# MM2017-18_uC_Main.net
KiCad netlist of a schematic drawn in EAGLE
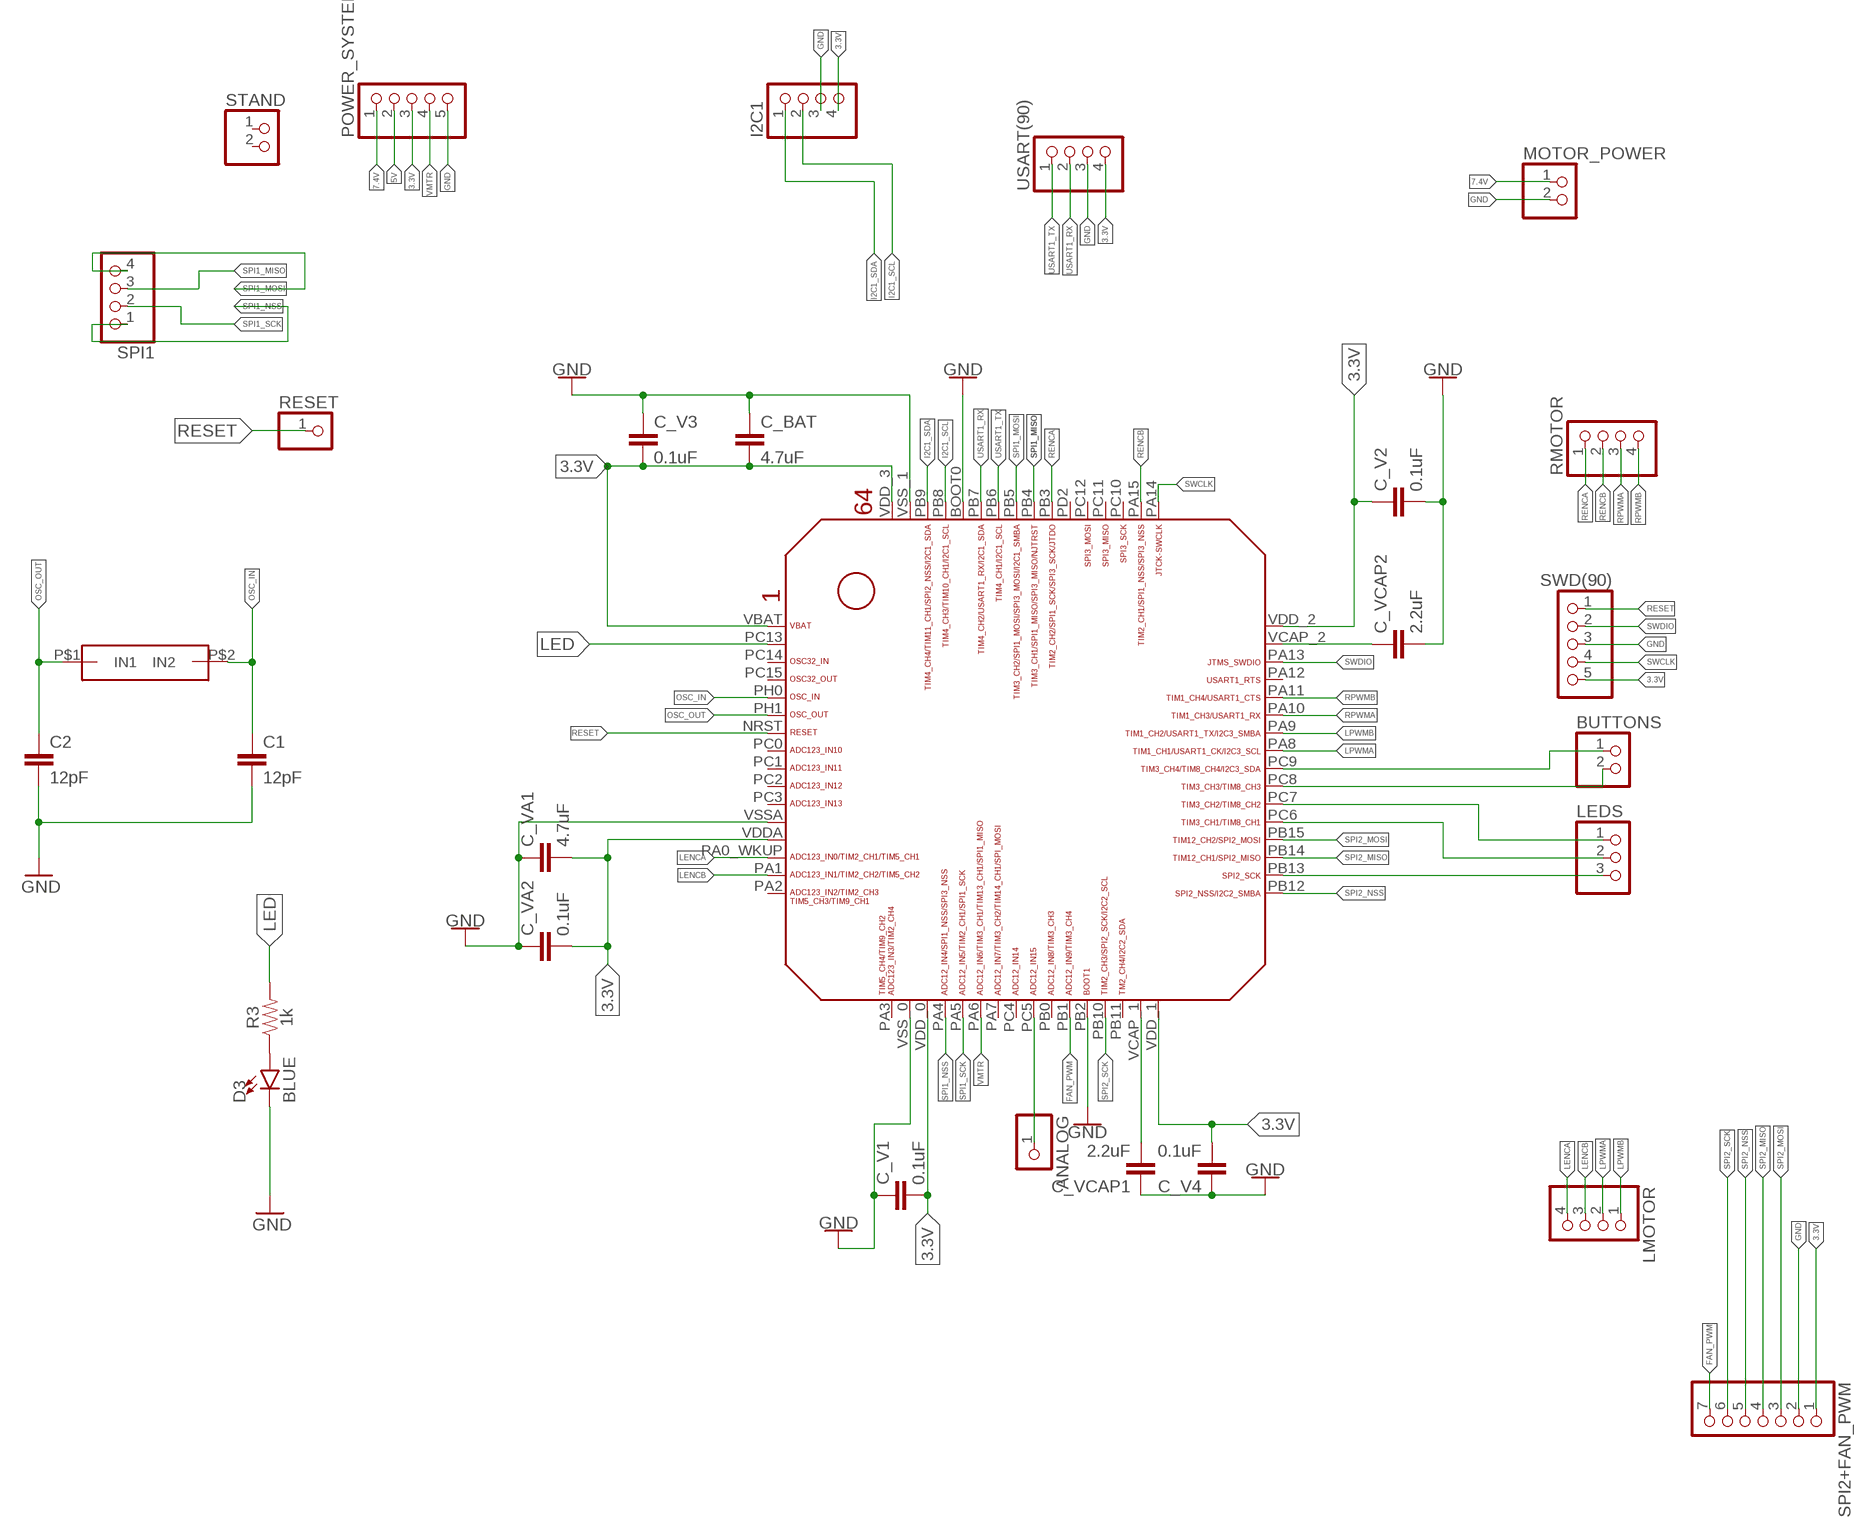
[diagram p0: schematic, sheet 1]

(export (version "E")
  (design (tool "Eeschema 10.0.6"))
  (components
    (comp (ref "ANALOG")
      (value "PINHD-1X1")
      (footprint "eagle-import:1X01")
      (libsource (lib "eagle-import") (part "PINHD-1X1"))
    )
    (comp (ref "BUTTONS")
      (value "PINHD-1X2")
      (footprint "eagle-import:1X02")
      (libsource (lib "eagle-import") (part "PINHD-1X2"))
    )
    (comp (ref "C1")
      (value "12pF")
      (footprint "eagle-import:0603")
      (libsource (lib "eagle-import") (part "22PF-0603-50V-5%"))
    )
    (comp (ref "C2")
      (value "12pF")
      (footprint "eagle-import:0603")
      (libsource (lib "eagle-import") (part "22PF-0603-50V-5%"))
    )
    (comp (ref "C_BAT")
      (value "4.7uF")
      (footprint "eagle-import:0805")
      (libsource (lib "eagle-import") (part "22UF-0805-6.3V-20%"))
    )
    (comp (ref "C_V1")
      (value "0.1uF")
      (footprint "eagle-import:0805")
      (libsource (lib "eagle-import") (part "22UF-0805-6.3V-20%"))
    )
    (comp (ref "C_V2")
      (value "0.1uF")
      (footprint "eagle-import:0805")
      (libsource (lib "eagle-import") (part "22UF-0805-6.3V-20%"))
    )
    (comp (ref "C_V3")
      (value "0.1uF")
      (footprint "eagle-import:0805")
      (libsource (lib "eagle-import") (part "22UF-0805-6.3V-20%"))
    )
    (comp (ref "C_V4")
      (value "0.1uF")
      (footprint "eagle-import:0805")
      (libsource (lib "eagle-import") (part "22UF-0805-6.3V-20%"))
    )
    (comp (ref "C_VA1")
      (value "4.7uF")
      (footprint "eagle-import:0805")
      (libsource (lib "eagle-import") (part "22UF-0805-6.3V-20%"))
    )
    (comp (ref "C_VA2")
      (value "0.1uF")
      (footprint "eagle-import:0805")
      (libsource (lib "eagle-import") (part "22UF-0805-6.3V-20%"))
    )
    (comp (ref "C_VCAP1")
      (value "2.2uF")
      (footprint "eagle-import:0805")
      (libsource (lib "eagle-import") (part "22UF-0805-6.3V-20%"))
    )
    (comp (ref "C_VCAP2")
      (value "2.2uF")
      (footprint "eagle-import:0805")
      (libsource (lib "eagle-import") (part "22UF-0805-6.3V-20%"))
    )
    (comp (ref "D3")
      (value "BLUE")
      (footprint "eagle-import:LED-1206")
      (libsource (lib "eagle-import") (part "LED-BLUE1206"))
    )
    (comp (ref "I2C1")
      (value "PINHD-1X4")
      (footprint "eagle-import:1X04")
      (libsource (lib "eagle-import") (part "PINHD-1X4"))
    )
    (comp (ref "LEDS")
      (value "PINHD-1X3")
      (footprint "eagle-import:1X03")
      (libsource (lib "eagle-import") (part "PINHD-1X3"))
    )
    (comp (ref "LMOTOR")
      (value "PINHD-1X4")
      (footprint "eagle-import:1X04")
      (libsource (lib "eagle-import") (part "PINHD-1X4"))
    )
    (comp (ref "MOTOR_POWER")
      (value "PINHD-1X2")
      (footprint "eagle-import:1X02")
      (libsource (lib "eagle-import") (part "PINHD-1X2"))
    )
    (comp (ref "POWER_SYSTEM")
      (value "PINHD-1X5")
      (footprint "eagle-import:1X05")
      (libsource (lib "eagle-import") (part "PINHD-1X5"))
    )
    (comp (ref "R3")
      (value "1k")
      (footprint "eagle-import:0805")
      (libsource (lib "eagle-import") (part "0.75OHM-0805-1/4W-1%"))
    )
    (comp (ref "RESET")
      (value "PINHD-1X1")
      (footprint "eagle-import:1X01")
      (libsource (lib "eagle-import") (part "PINHD-1X1"))
    )
    (comp (ref "RMOTOR")
      (value "PINHD-1X4")
      (footprint "eagle-import:1X04")
      (libsource (lib "eagle-import") (part "PINHD-1X4"))
    )
    (comp (ref "SPI1")
      (value "PINHD-1X4")
      (footprint "eagle-import:1X04")
      (libsource (lib "eagle-import") (part "PINHD-1X4"))
    )
    (comp (ref "SPI2+FAN_PWM")
      (value "PINHD-1X7")
      (footprint "eagle-import:1X07")
      (libsource (lib "eagle-import") (part "PINHD-1X7"))
    )
    (comp (ref "STAND")
      (value "PINHD-1X2")
      (footprint "eagle-import:1X02")
      (libsource (lib "eagle-import") (part "PINHD-1X2"))
    )
    (comp (ref "SWD(90)")
      (value "PINHD-1X5")
      (footprint "eagle-import:1X05")
      (libsource (lib "eagle-import") (part "PINHD-1X5"))
    )
    (comp (ref "U$1")
      (value "STM32F405/415_LQFP64")
      (footprint "eagle-import:STM32F405_415_LQFP64")
      (libsource (lib "eagle-import") (part "STM32F405/415_LQFP64"))
    )
    (comp (ref "U$2")
      (value "OSC")
      (footprint "eagle-import:OSC")
      (libsource (lib "eagle-import") (part "OSC"))
    )
    (comp (ref "USART(90)")
      (value "PINHD-1X4")
      (footprint "eagle-import:1X04")
      (libsource (lib "eagle-import") (part "PINHD-1X4"))
    )
  )
  (nets
    (net (code "1") (name "3.3V") (class "Default")
      (node (ref "C_BAT") (pin "2") (pinfunction "2_2") (pintype "passive"))
      (node (ref "C_V1") (pin "2") (pinfunction "2_2") (pintype "passive"))
      (node (ref "C_V2") (pin "1") (pinfunction "1_1") (pintype "passive"))
      (node (ref "C_V3") (pin "2") (pinfunction "2_2") (pintype "passive"))
      (node (ref "C_V4") (pin "2") (pinfunction "2_2") (pintype "passive"))
      (node (ref "C_VA1") (pin "2") (pinfunction "2_2") (pintype "passive"))
      (node (ref "C_VA2") (pin "2") (pinfunction "2_2") (pintype "passive"))
      (node (ref "I2C1") (pin "4") (pinfunction "4_4") (pintype "passive"))
      (node (ref "POWER_SYSTEM") (pin "3") (pinfunction "3_3") (pintype "passive"))
      (node (ref "SPI2+FAN_PWM") (pin "1") (pinfunction "1_1") (pintype "passive"))
      (node (ref "SWD(90)") (pin "5") (pinfunction "5_5") (pintype "passive"))
      (node (ref "U$1") (pin "VBAT") (pinfunction "VBAT_VBAT") (pintype "bidirectional"))
      (node (ref "U$1") (pin "VDDA") (pinfunction "VDDA_VDDA") (pintype "bidirectional"))
      (node (ref "U$1") (pin "VDD_0") (pinfunction "VDD_0_VDD_0") (pintype "bidirectional"))
      (node (ref "U$1") (pin "VDD_1") (pinfunction "VDD_1_VDD_1") (pintype "bidirectional"))
      (node (ref "U$1") (pin "VDD_2") (pinfunction "VDD_2_VDD_2") (pintype "bidirectional"))
      (node (ref "U$1") (pin "VDD_3") (pinfunction "VDD_3_VDD_3") (pintype "bidirectional"))
      (node (ref "USART(90)") (pin "4") (pinfunction "4_4") (pintype "passive"))
    )
    (net (code "2") (name "5V") (class "Default")
      (node (ref "POWER_SYSTEM") (pin "2") (pinfunction "2_2") (pintype "passive"))
    )
    (net (code "3") (name "7.4V") (class "Default")
      (node (ref "MOTOR_POWER") (pin "1") (pinfunction "1_1") (pintype "passive"))
      (node (ref "POWER_SYSTEM") (pin "1") (pinfunction "1_1") (pintype "passive"))
    )
    (net (code "4") (name "FAN_PWM") (class "Default")
      (node (ref "SPI2+FAN_PWM") (pin "7") (pinfunction "7_7") (pintype "passive"))
      (node (ref "U$1") (pin "PB1") (pinfunction "PB1_PB1") (pintype "bidirectional"))
    )
    (net (code "5") (name "GND") (class "Default")
      (node (ref "C1") (pin "2") (pinfunction "2_2") (pintype "passive"))
      (node (ref "C2") (pin "2") (pinfunction "2_2") (pintype "passive"))
      (node (ref "C_BAT") (pin "1") (pinfunction "1_1") (pintype "passive"))
      (node (ref "C_V1") (pin "1") (pinfunction "1_1") (pintype "passive"))
      (node (ref "C_V2") (pin "2") (pinfunction "2_2") (pintype "passive"))
      (node (ref "C_V3") (pin "1") (pinfunction "1_1") (pintype "passive"))
      (node (ref "C_V4") (pin "1") (pinfunction "1_1") (pintype "passive"))
      (node (ref "C_VA1") (pin "1") (pinfunction "1_1") (pintype "passive"))
      (node (ref "C_VA2") (pin "1") (pinfunction "1_1") (pintype "passive"))
      (node (ref "C_VCAP1") (pin "1") (pinfunction "1_1") (pintype "passive"))
      (node (ref "C_VCAP2") (pin "2") (pinfunction "2_2") (pintype "passive"))
      (node (ref "D3") (pin "C") (pinfunction "C_C") (pintype "passive"))
      (node (ref "I2C1") (pin "3") (pinfunction "3_3") (pintype "passive"))
      (node (ref "MOTOR_POWER") (pin "2") (pinfunction "2_2") (pintype "passive"))
      (node (ref "POWER_SYSTEM") (pin "5") (pinfunction "5_5") (pintype "passive"))
      (node (ref "SPI2+FAN_PWM") (pin "2") (pinfunction "2_2") (pintype "passive"))
      (node (ref "SWD(90)") (pin "3") (pinfunction "3_3") (pintype "passive"))
      (node (ref "U$1") (pin "BOOT0") (pinfunction "BOOT0_BOOT0") (pintype "bidirectional"))
      (node (ref "U$1") (pin "PB2") (pinfunction "PB2_PB2") (pintype "bidirectional"))
      (node (ref "U$1") (pin "VSSA") (pinfunction "VSSA_VSSA") (pintype "bidirectional"))
      (node (ref "U$1") (pin "VSS_0") (pinfunction "VSS_0_VSS_0") (pintype "bidirectional"))
      (node (ref "U$1") (pin "VSS_1") (pinfunction "VSS_1_VSS_1") (pintype "bidirectional"))
      (node (ref "USART(90)") (pin "3") (pinfunction "3_3") (pintype "passive"))
    )
    (net (code "6") (name "I2C1_SCL") (class "Default")
      (node (ref "I2C1") (pin "2") (pinfunction "2_2") (pintype "passive"))
      (node (ref "U$1") (pin "PB8") (pinfunction "PB8_PB8") (pintype "bidirectional"))
    )
    (net (code "7") (name "I2C1_SDA") (class "Default")
      (node (ref "I2C1") (pin "1") (pinfunction "1_1") (pintype "passive"))
      (node (ref "U$1") (pin "PB9") (pinfunction "PB9_PB9") (pintype "bidirectional"))
    )
    (net (code "8") (name "LED") (class "Default")
      (node (ref "R3") (pin "2") (pinfunction "2_2") (pintype "passive"))
      (node (ref "U$1") (pin "PC13") (pinfunction "PC13_PC13") (pintype "bidirectional"))
    )
    (net (code "9") (name "LENCA") (class "Default")
      (node (ref "LMOTOR") (pin "4") (pinfunction "4_4") (pintype "passive"))
      (node (ref "U$1") (pin "PA0_WKUP") (pinfunction "PA0_AKUP_PA0_WKUP") (pintype "bidirectional"))
    )
    (net (code "10") (name "LENCB") (class "Default")
      (node (ref "LMOTOR") (pin "3") (pinfunction "3_3") (pintype "passive"))
      (node (ref "U$1") (pin "PA1") (pinfunction "PA1_PA1") (pintype "bidirectional"))
    )
    (net (code "11") (name "LPWMA") (class "Default")
      (node (ref "LMOTOR") (pin "2") (pinfunction "2_2") (pintype "passive"))
      (node (ref "U$1") (pin "PA8") (pinfunction "PA8_PA8") (pintype "bidirectional"))
    )
    (net (code "12") (name "LPWMB") (class "Default")
      (node (ref "LMOTOR") (pin "1") (pinfunction "1_1") (pintype "passive"))
      (node (ref "U$1") (pin "PA9") (pinfunction "PA9_PA9") (pintype "bidirectional"))
    )
    (net (code "13") (name "Net-(ANALOG-Pad1)") (class "Default")
      (node (ref "ANALOG") (pin "1") (pinfunction "1_1") (pintype "passive"))
      (node (ref "U$1") (pin "PC5") (pinfunction "PC5_PC5") (pintype "bidirectional"))
    )
    (net (code "14") (name "Net-(BUTTONS-Pad1)") (class "Default")
      (node (ref "BUTTONS") (pin "1") (pinfunction "1_1") (pintype "passive"))
      (node (ref "U$1") (pin "PC9") (pinfunction "PC9_PC9") (pintype "bidirectional"))
    )
    (net (code "15") (name "Net-(BUTTONS-Pad2)") (class "Default")
      (node (ref "BUTTONS") (pin "2") (pinfunction "2_2") (pintype "passive"))
      (node (ref "U$1") (pin "PC8") (pinfunction "PC8_PC8") (pintype "bidirectional"))
    )
    (net (code "16") (name "Net-(C_VCAP1-Pad2)") (class "Default")
      (node (ref "C_VCAP1") (pin "2") (pinfunction "2_2") (pintype "passive"))
      (node (ref "U$1") (pin "VCAP_1") (pinfunction "VCAP_1_VCAP_1") (pintype "bidirectional"))
    )
    (net (code "17") (name "Net-(C_VCAP2-Pad1)") (class "Default")
      (node (ref "C_VCAP2") (pin "1") (pinfunction "1_1") (pintype "passive"))
      (node (ref "U$1") (pin "VCAP_2") (pinfunction "VCAP_2_VCAP_2") (pintype "bidirectional"))
    )
    (net (code "18") (name "Net-(D3-PadA)") (class "Default")
      (node (ref "D3") (pin "A") (pinfunction "A_A") (pintype "passive"))
      (node (ref "R3") (pin "1") (pinfunction "1_1") (pintype "passive"))
    )
    (net (code "19") (name "Net-(LEDS-Pad1)") (class "Default")
      (node (ref "LEDS") (pin "1") (pinfunction "1_1") (pintype "passive"))
      (node (ref "U$1") (pin "PC7") (pinfunction "PC7_PC7") (pintype "bidirectional"))
    )
    (net (code "20") (name "Net-(LEDS-Pad2)") (class "Default")
      (node (ref "LEDS") (pin "2") (pinfunction "2_2") (pintype "passive"))
      (node (ref "U$1") (pin "PC6") (pinfunction "PC6_PC6") (pintype "bidirectional"))
    )
    (net (code "21") (name "Net-(LEDS-Pad3)") (class "Default")
      (node (ref "LEDS") (pin "3") (pinfunction "3_3") (pintype "passive"))
      (node (ref "U$1") (pin "PB13") (pinfunction "PB13_PB13") (pintype "bidirectional"))
    )
    (net (code "22") (name "OSC_IN") (class "Default")
      (node (ref "C1") (pin "1") (pinfunction "1_1") (pintype "passive"))
      (node (ref "U$1") (pin "PH0") (pinfunction "PH0_PH0") (pintype "bidirectional"))
      (node (ref "U$2") (pin "P$2") (pinfunction "IN2_P$2") (pintype "bidirectional"))
    )
    (net (code "23") (name "OSC_OUT") (class "Default")
      (node (ref "C2") (pin "1") (pinfunction "1_1") (pintype "passive"))
      (node (ref "U$1") (pin "PH1") (pinfunction "PH1_PH1") (pintype "bidirectional"))
      (node (ref "U$2") (pin "P$1") (pinfunction "IN1_P$1") (pintype "bidirectional"))
    )
    (net (code "24") (name "RENCA") (class "Default")
      (node (ref "RMOTOR") (pin "1") (pinfunction "1_1") (pintype "passive"))
      (node (ref "U$1") (pin "PB3") (pinfunction "PB3_PB3") (pintype "bidirectional"))
    )
    (net (code "25") (name "RENCB") (class "Default")
      (node (ref "RMOTOR") (pin "2") (pinfunction "2_2") (pintype "passive"))
      (node (ref "U$1") (pin "PA15") (pinfunction "PA15_PA15") (pintype "bidirectional"))
    )
    (net (code "26") (name "RESET") (class "Default")
      (node (ref "RESET") (pin "1") (pinfunction "1_1") (pintype "passive"))
      (node (ref "SWD(90)") (pin "1") (pinfunction "1_1") (pintype "passive"))
      (node (ref "U$1") (pin "NRST") (pinfunction "NRST_NRST") (pintype "bidirectional"))
    )
    (net (code "27") (name "RPWMA") (class "Default")
      (node (ref "RMOTOR") (pin "3") (pinfunction "3_3") (pintype "passive"))
      (node (ref "U$1") (pin "PA10") (pinfunction "PA10_PA10") (pintype "bidirectional"))
    )
    (net (code "28") (name "RPWMB") (class "Default")
      (node (ref "RMOTOR") (pin "4") (pinfunction "4_4") (pintype "passive"))
      (node (ref "U$1") (pin "PA11") (pinfunction "PA11_PA11") (pintype "bidirectional"))
    )
    (net (code "29") (name "SPI1_MISO") (class "Default")
      (node (ref "SPI1") (pin "3") (pinfunction "3_3") (pintype "passive"))
      (node (ref "U$1") (pin "PB4") (pinfunction "PB4_PB4") (pintype "bidirectional"))
    )
    (net (code "30") (name "SPI1_MOSI") (class "Default")
      (node (ref "SPI1") (pin "4") (pinfunction "4_4") (pintype "passive"))
      (node (ref "U$1") (pin "PB5") (pinfunction "PB5_PB5") (pintype "bidirectional"))
    )
    (net (code "31") (name "SPI1_NSS") (class "Default")
      (node (ref "SPI1") (pin "1") (pinfunction "1_1") (pintype "passive"))
      (node (ref "U$1") (pin "PA4") (pinfunction "PA4_PA4") (pintype "bidirectional"))
    )
    (net (code "32") (name "SPI1_SCK") (class "Default")
      (node (ref "SPI1") (pin "2") (pinfunction "2_2") (pintype "passive"))
      (node (ref "U$1") (pin "PA5") (pinfunction "PA5_PA5") (pintype "bidirectional"))
    )
    (net (code "33") (name "SPI2_MISO") (class "Default")
      (node (ref "SPI2+FAN_PWM") (pin "4") (pinfunction "4_4") (pintype "passive"))
      (node (ref "U$1") (pin "PB14") (pinfunction "PB14_PB14") (pintype "bidirectional"))
    )
    (net (code "34") (name "SPI2_MOSI") (class "Default")
      (node (ref "SPI2+FAN_PWM") (pin "3") (pinfunction "3_3") (pintype "passive"))
      (node (ref "U$1") (pin "PB15") (pinfunction "PB15_PB15") (pintype "bidirectional"))
    )
    (net (code "35") (name "SPI2_NSS") (class "Default")
      (node (ref "SPI2+FAN_PWM") (pin "5") (pinfunction "5_5") (pintype "passive"))
      (node (ref "U$1") (pin "PB12") (pinfunction "PB12_PB12") (pintype "bidirectional"))
    )
    (net (code "36") (name "SPI2_SCK") (class "Default")
      (node (ref "SPI2+FAN_PWM") (pin "6") (pinfunction "6_6") (pintype "passive"))
      (node (ref "U$1") (pin "PB10") (pinfunction "PB10_PB10") (pintype "bidirectional"))
    )
    (net (code "37") (name "SWCLK") (class "Default")
      (node (ref "SWD(90)") (pin "4") (pinfunction "4_4") (pintype "passive"))
      (node (ref "U$1") (pin "PA14") (pinfunction "PA14_PA14") (pintype "bidirectional"))
    )
    (net (code "38") (name "SWDIO") (class "Default")
      (node (ref "SWD(90)") (pin "2") (pinfunction "2_2") (pintype "passive"))
      (node (ref "U$1") (pin "PA13") (pinfunction "PA13_PA13") (pintype "bidirectional"))
    )
    (net (code "39") (name "USART1_RX") (class "Default")
      (node (ref "U$1") (pin "PB7") (pinfunction "PB7_PB7") (pintype "bidirectional"))
      (node (ref "USART(90)") (pin "2") (pinfunction "2_2") (pintype "passive"))
    )
    (net (code "40") (name "USART1_TX") (class "Default")
      (node (ref "U$1") (pin "PB6") (pinfunction "PB6_PB6") (pintype "bidirectional"))
      (node (ref "USART(90)") (pin "1") (pinfunction "1_1") (pintype "passive"))
    )
    (net (code "41") (name "VMTR") (class "Default")
      (node (ref "POWER_SYSTEM") (pin "4") (pinfunction "4_4") (pintype "passive"))
      (node (ref "U$1") (pin "PA6") (pinfunction "PA6_PA6") (pintype "bidirectional"))
    )
    (net (code "42") (name "unconnected-(STAND-Pad1)") (class "Default")
      (node (ref "STAND") (pin "1") (pinfunction "1_1") (pintype "passive"))
    )
    (net (code "43") (name "unconnected-(STAND-Pad2)") (class "Default")
      (node (ref "STAND") (pin "2") (pinfunction "2_2") (pintype "passive"))
    )
    (net (code "44") (name "unconnected-(U$1-PadPA2)") (class "Default")
      (node (ref "U$1") (pin "PA2") (pinfunction "PA2_PA2") (pintype "bidirectional"))
    )
    (net (code "45") (name "unconnected-(U$1-PadPA3)") (class "Default")
      (node (ref "U$1") (pin "PA3") (pinfunction "PA3_PA3") (pintype "bidirectional"))
    )
    (net (code "46") (name "unconnected-(U$1-PadPA7)") (class "Default")
      (node (ref "U$1") (pin "PA7") (pinfunction "PA7_PA7") (pintype "bidirectional"))
    )
    (net (code "47") (name "unconnected-(U$1-PadPA12)") (class "Default")
      (node (ref "U$1") (pin "PA12") (pinfunction "PA12_PA12") (pintype "bidirectional"))
    )
    (net (code "48") (name "unconnected-(U$1-PadPB0)") (class "Default")
      (node (ref "U$1") (pin "PB0") (pinfunction "PB0_PB0") (pintype "bidirectional"))
    )
    (net (code "49") (name "unconnected-(U$1-PadPB11)") (class "Default")
      (node (ref "U$1") (pin "PB11") (pinfunction "PB11_PB11") (pintype "bidirectional"))
    )
    (net (code "50") (name "unconnected-(U$1-PadPC0)") (class "Default")
      (node (ref "U$1") (pin "PC0") (pinfunction "PC0_PC0") (pintype "bidirectional"))
    )
    (net (code "51") (name "unconnected-(U$1-PadPC1)") (class "Default")
      (node (ref "U$1") (pin "PC1") (pinfunction "PC1_PC1") (pintype "bidirectional"))
    )
    (net (code "52") (name "unconnected-(U$1-PadPC2)") (class "Default")
      (node (ref "U$1") (pin "PC2") (pinfunction "PC2_PC2") (pintype "bidirectional"))
    )
    (net (code "53") (name "unconnected-(U$1-PadPC3)") (class "Default")
      (node (ref "U$1") (pin "PC3") (pinfunction "PC3_PC3") (pintype "bidirectional"))
    )
    (net (code "54") (name "unconnected-(U$1-PadPC4)") (class "Default")
      (node (ref "U$1") (pin "PC4") (pinfunction "PC4_PC4") (pintype "bidirectional"))
    )
    (net (code "55") (name "unconnected-(U$1-PadPC10)") (class "Default")
      (node (ref "U$1") (pin "PC10") (pinfunction "PC10_PC10") (pintype "bidirectional"))
    )
    (net (code "56") (name "unconnected-(U$1-PadPC11)") (class "Default")
      (node (ref "U$1") (pin "PC11") (pinfunction "PC11_PC11") (pintype "bidirectional"))
    )
    (net (code "57") (name "unconnected-(U$1-PadPC12)") (class "Default")
      (node (ref "U$1") (pin "PC12") (pinfunction "PC12_PC12") (pintype "bidirectional"))
    )
    (net (code "58") (name "unconnected-(U$1-PadPC14)") (class "Default")
      (node (ref "U$1") (pin "PC14") (pinfunction "PC14_PC14") (pintype "bidirectional"))
    )
    (net (code "59") (name "unconnected-(U$1-PadPC15)") (class "Default")
      (node (ref "U$1") (pin "PC15") (pinfunction "PC15_PC15") (pintype "bidirectional"))
    )
    (net (code "60") (name "unconnected-(U$1-PadPD2)") (class "Default")
      (node (ref "U$1") (pin "PD2") (pinfunction "PD2_PD2") (pintype "bidirectional"))
    )
  )
)
